# Voltage_Divider.net
KiCad netlist of a schematic drawn in Altium Designer
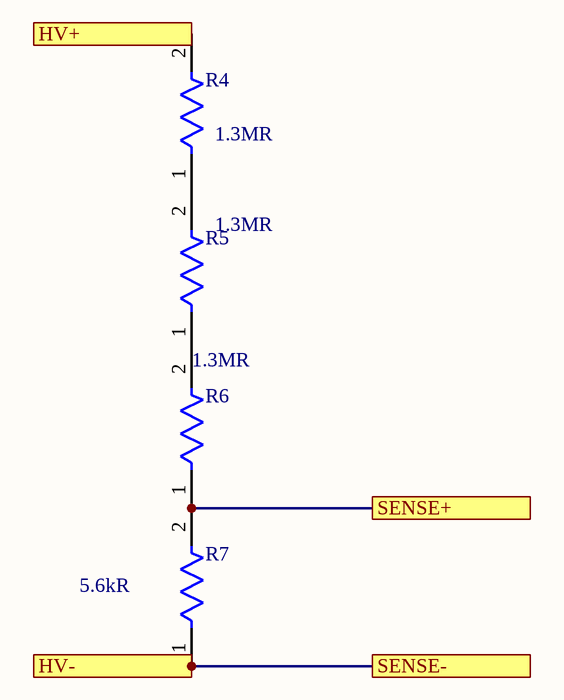
[diagram p0: Voltage Divider.SchDoc]

(export (version "E")
  (design (tool "Eeschema 10.0.6"))
  (components
    (comp (ref "R4")
      (value "KTR10EZPJ135")
      (footprint "FP-KTR10-MFG")
      (description "Res Thick Film 0805 1.3MΩ 5% 0.125W ±200ppm/°C Automotive Paper T/R")
      (fields (field (name "TOLERANCE") "5%") (field (name "RESISTANCE") "1.3MR"))
      (libsource (lib "Altium Content Vault") (part "1029c3af85768c4190bb7ad29bc67b5"))
    )
    (comp (ref "R5")
      (value "KTR10EZPJ135")
      (footprint "FP-KTR10-MFG")
      (description "Res Thick Film 0805 1.3MΩ 5% 0.125W ±200ppm/°C Automotive Paper T/R")
      (fields (field (name "TOLERANCE") "5%") (field (name "RESISTANCE") "1.3MR"))
      (libsource (lib "Altium Content Vault") (part "1029c3af85768c4190bb7ad29bc67b5"))
    )
    (comp (ref "R6")
      (value "KTR10EZPJ135")
      (footprint "FP-KTR10-MFG")
      (description "Res Thick Film 0805 1.3MΩ 5% 0.125W ±200ppm/°C Automotive Paper T/R")
      (fields (field (name "TOLERANCE") "5%") (field (name "RESISTANCE") "1.3MR"))
      (libsource (lib "Altium Content Vault") (part "1029c3af85768c4190bb7ad29bc67b5"))
    )
    (comp (ref "R7")
      (value "CRCW06035K60FKEA")
      (footprint "FP-CRCW0603-e3-MFG")
      (description "RES Thick Film, 5.6kΩ, 1%, 0.1W, 100ppm/°C, 0603")
      (fields (field (name "TOLERANCE") "1%") (field (name "RESISTANCE") "5.6kR"))
      (libsource (lib "Altium Content Vault") (part "1029c3af85768c4190bb7ad29bc67b5"))
    )
  )
  (nets
    (net (code "1") (name "/HV+") (class "Default")
      (node (ref "R4") (pin "2") (pinfunction "2_2") (pintype "passive"))
    )
    (net (code "2") (name "/HV-") (class "Default")
      (node (ref "R7") (pin "1") (pinfunction "1_1") (pintype "passive"))
    )
    (net (code "3") (name "/SENSE+") (class "Default")
      (node (ref "R6") (pin "1") (pinfunction "1_1") (pintype "passive"))
      (node (ref "R7") (pin "2") (pinfunction "2_2") (pintype "passive"))
    )
    (net (code "4") (name "Net-(R4-Pad1)") (class "Default")
      (node (ref "R4") (pin "1") (pinfunction "1_1") (pintype "passive"))
      (node (ref "R5") (pin "2") (pinfunction "2_2") (pintype "passive"))
    )
    (net (code "5") (name "Net-(R5-Pad1)") (class "Default")
      (node (ref "R5") (pin "1") (pinfunction "1_1") (pintype "passive"))
      (node (ref "R6") (pin "2") (pinfunction "2_2") (pintype "passive"))
    )
  )
)
